# Microcontroller.net
KiCad netlist of a schematic drawn in Altium Designer
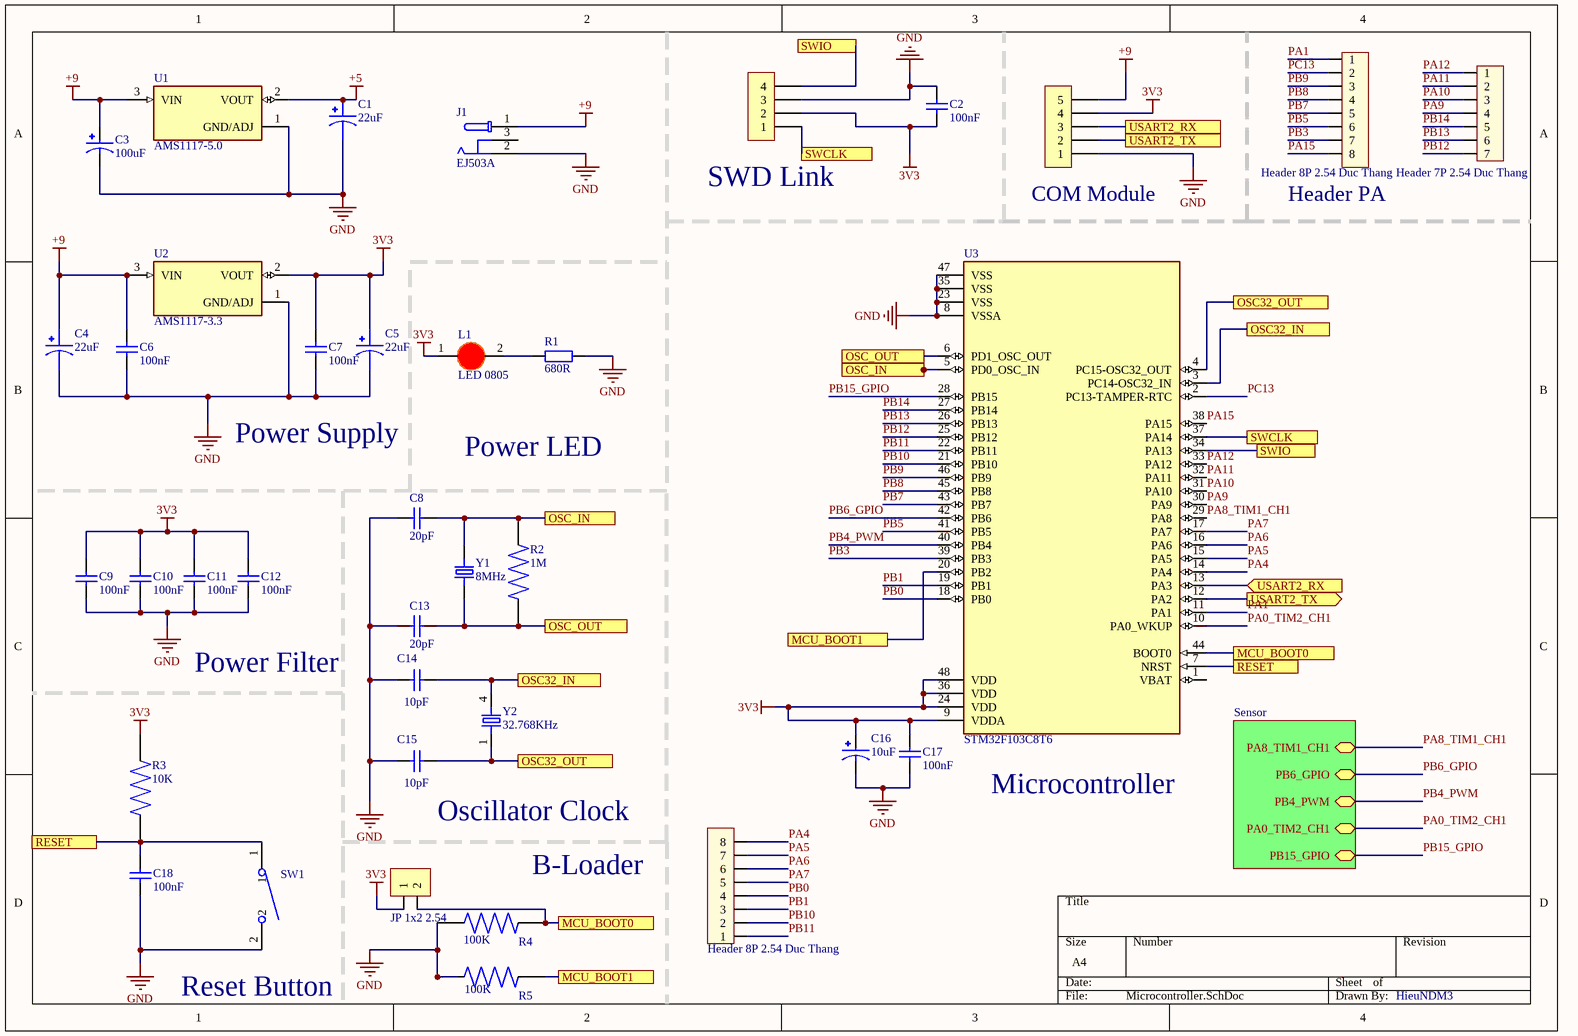
[diagram p0: Microcontroller.SchDoc]

(export (version "E")
  (design (tool "Eeschema 10.0.6"))
  (components
    (comp (ref "C1")
      (value "22uF")
      (footprint "MyPCBLib:CAPPRD200W50D550H1250")
      (description "22ÂµF 25V Aluminum Electrolytic Capacitors Radial, Can 2000 Hrs @ 85Â°C")
      (fields (field (name "MF") "Nichicon") (field (name "MP") "UVR1E220MDD"))
      (libsource (lib "MyScheLib") (part "UVR1E220MDD"))
    )
    (comp (ref "C2")
      (value "100nF")
      (footprint "MyPCBLib:WCAP-CSST_0805_L2W1.25H1.25")
      (fields
        (field (name "MANUFACTURER PART NUMBER") "885382207007")
        (field (name "MANUFACTURER") "Wurth Elektronik")
      )
      (libsource (lib "MyScheLib") (part "885382207007"))
    )
    (comp (ref "C3")
      (value "100uF")
      (footprint "MyPCBLib:CAPPRD500W60D1000H1250")
      (description "CAP ALUM 100UF 20% 35V RADIAL")
      (fields (field (name "MF") "Panasonic") (field (name "MP") "EEUTA1V101"))
      (libsource (lib "MyScheLib") (part "EEUTA1V101"))
    )
    (comp (ref "C4")
      (value "22uF")
      (footprint "MyPCBLib:CAPPRD200W50D550H1250")
      (description "22ÂµF 25V Aluminum Electrolytic Capacitors Radial, Can 2000 Hrs @ 85Â°C")
      (fields (field (name "MF") "Nichicon") (field (name "MP") "UVR1E220MDD"))
      (libsource (lib "MyScheLib") (part "UVR1E220MDD"))
    )
    (comp (ref "C5")
      (value "22uF")
      (footprint "MyPCBLib:CAPPRD200W50D550H1250")
      (description "22ÂµF 25V Aluminum Electrolytic Capacitors Radial, Can 2000 Hrs @ 85Â°C")
      (fields (field (name "MF") "Nichicon") (field (name "MP") "UVR1E220MDD"))
      (libsource (lib "MyScheLib") (part "UVR1E220MDD"))
    )
    (comp (ref "C6")
      (value "100nF")
      (footprint "MyPCBLib:WCAP-CSST_0805_L2W1.25H1.25")
      (fields
        (field (name "MANUFACTURER PART NUMBER") "885382207007")
        (field (name "MANUFACTURER") "Wurth Elektronik")
      )
      (libsource (lib "MyScheLib") (part "885382207007"))
    )
    (comp (ref "C7")
      (value "100nF")
      (footprint "MyPCBLib:WCAP-CSST_0805_L2W1.25H1.25")
      (fields
        (field (name "MANUFACTURER PART NUMBER") "885382207007")
        (field (name "MANUFACTURER") "Wurth Elektronik")
      )
      (libsource (lib "MyScheLib") (part "885382207007"))
    )
    (comp (ref "C8")
      (value "20pF")
      (footprint "tu 0805")
      (description "Dán")
      (libsource (lib "Tu dien") (part "Tu 0805 20pF 50V 10%"))
    )
    (comp (ref "C9")
      (value "100nF")
      (footprint "MyPCBLib:WCAP-CSST_0805_L2W1.25H1.25")
      (fields
        (field (name "MANUFACTURER PART NUMBER") "885382207007")
        (field (name "MANUFACTURER") "Wurth Elektronik")
      )
      (libsource (lib "MyScheLib") (part "885382207007"))
    )
    (comp (ref "C10")
      (value "100nF")
      (footprint "MyPCBLib:WCAP-CSST_0805_L2W1.25H1.25")
      (fields
        (field (name "MANUFACTURER PART NUMBER") "885382207007")
        (field (name "MANUFACTURER") "Wurth Elektronik")
      )
      (libsource (lib "MyScheLib") (part "885382207007"))
    )
    (comp (ref "C11")
      (value "100nF")
      (footprint "MyPCBLib:WCAP-CSST_0805_L2W1.25H1.25")
      (fields
        (field (name "MANUFACTURER PART NUMBER") "885382207007")
        (field (name "MANUFACTURER") "Wurth Elektronik")
      )
      (libsource (lib "MyScheLib") (part "885382207007"))
    )
    (comp (ref "C12")
      (value "100nF")
      (footprint "MyPCBLib:WCAP-CSST_0805_L2W1.25H1.25")
      (fields
        (field (name "MANUFACTURER PART NUMBER") "885382207007")
        (field (name "MANUFACTURER") "Wurth Elektronik")
      )
      (libsource (lib "MyScheLib") (part "885382207007"))
    )
    (comp (ref "C13")
      (value "20pF")
      (footprint "tu 0805")
      (description "Dán")
      (libsource (lib "Tu dien") (part "Tu 0805 20pF 50V 10%"))
    )
    (comp (ref "C14")
      (value "10pF")
      (footprint "WCAP-CSGP_0805_L2W1.25H0.6_Reflow")
      (description "WCAP-CSGP Multilayer Ceramic Chip Capacitor, General Purpose, size 0805, NP0, 10pF, 50V")
      (fields
        (field (name "MANUFACTURER PART NUMBER") "885012007051")
        (field (name "MANUFACTURER") "Wurth Elektronik")
      )
      (libsource (lib "MyScheLib") (part "885012007051"))
    )
    (comp (ref "C15")
      (value "10pF")
      (footprint "WCAP-CSGP_0805_L2W1.25H0.6_Reflow")
      (description "WCAP-CSGP Multilayer Ceramic Chip Capacitor, General Purpose, size 0805, NP0, 10pF, 50V")
      (fields
        (field (name "MANUFACTURER PART NUMBER") "885012007051")
        (field (name "MANUFACTURER") "Wurth Elektronik")
      )
      (libsource (lib "MyScheLib") (part "885012007051"))
    )
    (comp (ref "C16")
      (value "10uF")
      (footprint "MyPCBLib:CAPMP7343X430N")
      (fields (field (name "MF") "Kemet") (field (name "MP") "T493X106K035AK6120"))
      (libsource (lib "MyScheLib") (part "T493X106K035AK6120"))
    )
    (comp (ref "C17")
      (value "100nF")
      (footprint "MyPCBLib:WCAP-CSST_0805_L2W1.25H1.25")
      (fields
        (field (name "MANUFACTURER PART NUMBER") "885382207007")
        (field (name "MANUFACTURER") "Wurth Elektronik")
      )
      (libsource (lib "MyScheLib") (part "885382207007"))
    )
    (comp (ref "C18")
      (value "100nF")
      (footprint "MyPCBLib:WCAP-CSST_0805_L2W1.25H1.25")
      (fields
        (field (name "MANUFACTURER PART NUMBER") "885382207007")
        (field (name "MANUFACTURER") "Wurth Elektronik")
      )
      (libsource (lib "MyScheLib") (part "885382207007"))
    )
    (comp (ref "H1")
      (value "Header 8P 2.54 Duc Thang")
      (footprint "XH2.54M-8")
      (description "Cắm")
      (libsource (lib "Header") (part "Header 8P 2.54 Duc Thang"))
    )
    (comp (ref "H2")
      (value "Header 7P 2.54 Duc Thang")
      (footprint "XH2.54M-7")
      (description "Cắm")
      (libsource (lib "Header") (part "Header 7P 2.54 Duc Thang"))
    )
    (comp (ref "H3")
      (value "~")
      (footprint "Header 4P DC 2.54")
      (description "Cắm")
      (libsource (lib "Header") (part "Header 4P 2.54 Duc Cong"))
    )
    (comp (ref "H4")
      (value "~")
      (footprint "XH2.54M-5")
      (description "Cắm")
      (libsource (lib "Header") (part "Header 5P 2.54 Duc Thang"))
    )
    (comp (ref "H5")
      (value "Header 8P 2.54 Duc Thang")
      (footprint "XH2.54M-8")
      (description "Cắm")
      (libsource (lib "") (part "Header 8P 2.54 Duc Thang_1"))
    )
    (comp (ref "J1")
      (value "EJ503A")
      (footprint "MPD_EJ503A")
      (description "Power Barrel Connector Jack 2.10mm ID (0.083), 5.50mm OD (0.217) Through Hole, Right Angle")
      (fields (field (name "MF") "MPD"))
      (libsource (lib "MyScheLib") (part "EJ503A"))
    )
    (comp (ref "JP1")
      (value "JP 1x2 2.54")
      (footprint "JP 1x2 DT")
      (description "Cắm")
      (libsource (lib "MyScheLib") (part "JP 1x2 2.54 Duc Thang"))
    )
    (comp (ref "L1")
      (value "LED 0805")
      (footprint "LED-0805-Red")
      (description "Dán")
      (libsource (lib "Led") (part "LED 0805 Do"))
    )
    (comp (ref "R1")
      (value "680R")
      (footprint "Tro SMD 0805")
      (description "Dán")
      (libsource (lib "Dien Tro") (part "Tro 0805 5% 680R"))
    )
    (comp (ref "R2")
      (value "1M")
      (footprint "MyPCBLib:RESC2012X65N")
      (description "Res Thin Film 0805 1M Ohm 0.1% 0.125W(1/8W) Â±15ppm/C Epoxy Pad SMD T/R")
      (fields (field (name "MP") "RP73D2A1M0BTDF"))
      (libsource (lib "MyScheLib") (part "RP73D2A1M0BTDF"))
    )
    (comp (ref "R3")
      (value "10K")
      (footprint "RESC2012X65N")
      (fields
        (field (name "MF") "{'manufacturer': u'Stackpole Electronics Inc'}")
        (field (name "MP") "RMCF0805FT10K0")
      )
      (libsource (lib "MyScheLib") (part "RMCF0805FT10K0"))
    )
    (comp (ref "R4")
      (value "100K")
      (footprint "RESC2012X65N")
      (fields
        (field (name "MF") "{'manufacturer': u'Stackpole Electronics Inc'}")
        (field (name "MP") "RMCF0805FT10K0")
      )
      (libsource (lib "MyScheLib") (part "RMCF0805FT10K0"))
    )
    (comp (ref "R5")
      (value "100K")
      (footprint "RESC2012X65N")
      (fields
        (field (name "MF") "{'manufacturer': u'Stackpole Electronics Inc'}")
        (field (name "MP") "RMCF0805FT10K0")
      )
      (libsource (lib "MyScheLib") (part "RMCF0805FT10K0"))
    )
    (comp (ref "SW1")
      (value "~")
      (footprint "MyPCBLib:SW_RS-032G05A3-SMRT")
      (description "Tactile Switch SPST-NO Top Actuated Surface Mount")
      (fields (field (name "MF") "C&K") (field (name "MP") "RS032G05A3SMRT"))
      (libsource (lib "MyScheLib") (part "RS-032G05A3-SMRT"))
    )
    (comp (ref "U1")
      (value "AMS1117-5.0")
      (footprint "SOT229P700X180-4N")
      (description "1A LOW DROPOUT VOLTAGE REGULATOR")
      (fields (field (name "MF") "ams"))
      (libsource (lib "MyScheLib") (part "AMS1117-5.0"))
    )
    (comp (ref "U2")
      (value "AMS1117-3.3")
      (footprint "SOT229P700X180-4N")
      (description "Sot223/Pkg 1-Amp 3.3-Volt Low Drop Out Voltage Regulatator")
      (fields (field (name "MF") "Advanced Monolithic Systems"))
      (libsource (lib "MyScheLib") (part "AMS1117-3.3"))
    )
    (comp (ref "U3")
      (value "STM32F103C8T6")
      (footprint "MyPCBLib:QFP50P900X900X160-48N")
      (description "ARM® Cortex®-M3 STM32F1 Microcontroller IC 32-Bit 72MHz 64KB (64K x 8) FLASH 48-LQFP (7x7)")
      (fields (field (name "MF") "STMicroelectronics"))
      (libsource (lib "MyScheLib") (part "STM32F103C8T6"))
    )
    (comp (ref "Y1")
      (value "8MHz")
      (footprint "MyPCBLib:XTAL_ECS-80-S-4X")
      (description "CRYSTAL T/H")
      (fields (field (name "MP") "ECS-80-S-4X"))
      (libsource (lib "MyScheLib") (part "ECS-80-S-4X"))
    )
    (comp (ref "Y2")
      (value "32.768KHz")
      (footprint "MyPCBLib:OSCL550P800X320X254-4N")
      (description "32.768kHz Â±100ppm Crystal 12.5pF 50 kOhms 4-SOJ, 5.50mm pitch")
      (fields (field (name "MP") "MC-306 32.7680K-A5: ROHS") (field (name "MF") "EPSON"))
      (libsource (lib "MyScheLib") (part "MC-306_32.7680K-A5{colon}_ROHS"))
    )
  )
  (nets
    (net (code "1") (name "+5") (class "Default")
      (node (ref "C1") (pin "1") (pinfunction "1_1") (pintype "passive"))
      (node (ref "U1") (pin "2") (pinfunction "VOUT_2") (pintype "bidirectional"))
    )
    (net (code "2") (name "+9") (class "Default")
      (node (ref "C3") (pin "P") (pinfunction "P_P") (pintype "passive"))
      (node (ref "C4") (pin "1") (pinfunction "1_1") (pintype "passive"))
      (node (ref "C6") (pin "2") (pinfunction "2_2") (pintype "passive"))
      (node (ref "H4") (pin "5") (pinfunction "5_5") (pintype "passive"))
      (node (ref "J1") (pin "1") (pinfunction "1_1") (pintype "passive"))
      (node (ref "U1") (pin "3") (pinfunction "VIN_3") (pintype "input"))
      (node (ref "U2") (pin "3") (pinfunction "VIN_3") (pintype "input"))
    )
    (net (code "3") (name "/MCU_BOOT0") (class "Default")
      (node (ref "JP1") (pin "2") (pinfunction "2_2") (pintype "passive"))
      (node (ref "R4") (pin "1") (pinfunction "1_1") (pintype "passive"))
      (node (ref "U3") (pin "44") (pinfunction "BOOT0_44") (pintype "input"))
    )
    (net (code "4") (name "/MCU_BOOT1") (class "Default")
      (node (ref "R5") (pin "1") (pinfunction "1_1") (pintype "passive"))
      (node (ref "U3") (pin "20") (pinfunction "PB2_20") (pintype "bidirectional"))
    )
    (net (code "5") (name "/OSC32_IN") (class "Default")
      (node (ref "C14") (pin "2") (pinfunction "2_2") (pintype "passive"))
      (node (ref "U3") (pin "3") (pinfunction "PC14-OSC32_IN_3") (pintype "bidirectional"))
      (node (ref "Y2") (pin "4") (pinfunction "4_4") (pintype "passive"))
    )
    (net (code "6") (name "/OSC32_OUT") (class "Default")
      (node (ref "C15") (pin "2") (pinfunction "2_2") (pintype "passive"))
      (node (ref "U3") (pin "4") (pinfunction "PC15-OSC32_OUT_4") (pintype "bidirectional"))
      (node (ref "Y2") (pin "1") (pinfunction "1_1") (pintype "passive"))
    )
    (net (code "7") (name "/OSC_IN") (class "Default")
      (node (ref "C8") (pin "1") (pinfunction "1_1") (pintype "passive"))
      (node (ref "R2") (pin "1") (pinfunction "1_1") (pintype "passive"))
      (node (ref "U3") (pin "5") (pinfunction "PD0_OSC_IN_5") (pintype "bidirectional"))
      (node (ref "Y1") (pin "2") (pinfunction "2_2") (pintype "passive"))
    )
    (net (code "8") (name "/OSC_OUT") (class "Default")
      (node (ref "C13") (pin "1") (pinfunction "1_1") (pintype "passive"))
      (node (ref "R2") (pin "2") (pinfunction "2_2") (pintype "passive"))
      (node (ref "U3") (pin "6") (pinfunction "PD1_OSC_OUT_6") (pintype "bidirectional"))
      (node (ref "Y1") (pin "1") (pinfunction "1_1") (pintype "passive"))
    )
    (net (code "9") (name "/PA0_TIM2_CH1") (class "Default")
      (node (ref "U3") (pin "10") (pinfunction "PA0_WKUP_10") (pintype "bidirectional"))
    )
    (net (code "10") (name "/PA1") (class "Default")
      (node (ref "H1") (pin "1") (pinfunction "1_1") (pintype "passive"))
      (node (ref "U3") (pin "11") (pinfunction "PA1_11") (pintype "bidirectional"))
    )
    (net (code "11") (name "/PA4") (class "Default")
      (node (ref "H5") (pin "8") (pinfunction "8_8") (pintype "passive"))
      (node (ref "U3") (pin "14") (pinfunction "PA4_14") (pintype "bidirectional"))
    )
    (net (code "12") (name "/PA5") (class "Default")
      (node (ref "H5") (pin "7") (pinfunction "7_7") (pintype "passive"))
      (node (ref "U3") (pin "15") (pinfunction "PA5_15") (pintype "bidirectional"))
    )
    (net (code "13") (name "/PA6") (class "Default")
      (node (ref "H5") (pin "6") (pinfunction "6_6") (pintype "passive"))
      (node (ref "U3") (pin "16") (pinfunction "PA6_16") (pintype "bidirectional"))
    )
    (net (code "14") (name "/PA7") (class "Default")
      (node (ref "H5") (pin "5") (pinfunction "5_5") (pintype "passive"))
      (node (ref "U3") (pin "17") (pinfunction "PA7_17") (pintype "bidirectional"))
    )
    (net (code "15") (name "/PA8_TIM1_CH1") (class "Default")
      (node (ref "U3") (pin "29") (pinfunction "PA8_29") (pintype "bidirectional"))
    )
    (net (code "16") (name "/PA9") (class "Default")
      (node (ref "H2") (pin "4") (pinfunction "4_4") (pintype "passive"))
      (node (ref "U3") (pin "30") (pinfunction "PA9_30") (pintype "bidirectional"))
    )
    (net (code "17") (name "/PA10") (class "Default")
      (node (ref "H2") (pin "3") (pinfunction "3_3") (pintype "passive"))
      (node (ref "U3") (pin "31") (pinfunction "PA10_31") (pintype "bidirectional"))
    )
    (net (code "18") (name "/PA11") (class "Default")
      (node (ref "H2") (pin "2") (pinfunction "2_2") (pintype "passive"))
      (node (ref "U3") (pin "32") (pinfunction "PA11_32") (pintype "bidirectional"))
    )
    (net (code "19") (name "/PA12") (class "Default")
      (node (ref "H2") (pin "1") (pinfunction "1_1") (pintype "passive"))
      (node (ref "U3") (pin "33") (pinfunction "PA12_33") (pintype "bidirectional"))
    )
    (net (code "20") (name "/PA15") (class "Default")
      (node (ref "H1") (pin "8") (pinfunction "8_8") (pintype "passive"))
      (node (ref "U3") (pin "38") (pinfunction "PA15_38") (pintype "bidirectional"))
    )
    (net (code "21") (name "/PB0") (class "Default")
      (node (ref "H5") (pin "4") (pinfunction "4_4") (pintype "passive"))
      (node (ref "U3") (pin "18") (pinfunction "PB0_18") (pintype "bidirectional"))
    )
    (net (code "22") (name "/PB1") (class "Default")
      (node (ref "H5") (pin "3") (pinfunction "3_3") (pintype "passive"))
      (node (ref "U3") (pin "19") (pinfunction "PB1_19") (pintype "bidirectional"))
    )
    (net (code "23") (name "/PB3") (class "Default")
      (node (ref "H1") (pin "7") (pinfunction "7_7") (pintype "passive"))
      (node (ref "U3") (pin "39") (pinfunction "PB3_39") (pintype "bidirectional"))
    )
    (net (code "24") (name "/PB4_PWM") (class "Default")
      (node (ref "U3") (pin "40") (pinfunction "PB4_40") (pintype "bidirectional"))
    )
    (net (code "25") (name "/PB5") (class "Default")
      (node (ref "H1") (pin "6") (pinfunction "6_6") (pintype "passive"))
      (node (ref "U3") (pin "41") (pinfunction "PB5_41") (pintype "bidirectional"))
    )
    (net (code "26") (name "/PB6_GPIO") (class "Default")
      (node (ref "U3") (pin "42") (pinfunction "PB6_42") (pintype "bidirectional"))
    )
    (net (code "27") (name "/PB7") (class "Default")
      (node (ref "H1") (pin "5") (pinfunction "5_5") (pintype "passive"))
      (node (ref "U3") (pin "43") (pinfunction "PB7_43") (pintype "bidirectional"))
    )
    (net (code "28") (name "/PB8") (class "Default")
      (node (ref "H1") (pin "4") (pinfunction "4_4") (pintype "passive"))
      (node (ref "U3") (pin "45") (pinfunction "PB8_45") (pintype "bidirectional"))
    )
    (net (code "29") (name "/PB9") (class "Default")
      (node (ref "H1") (pin "3") (pinfunction "3_3") (pintype "passive"))
      (node (ref "U3") (pin "46") (pinfunction "PB9_46") (pintype "bidirectional"))
    )
    (net (code "30") (name "/PB10") (class "Default")
      (node (ref "H5") (pin "2") (pinfunction "2_2") (pintype "passive"))
      (node (ref "U3") (pin "21") (pinfunction "PB10_21") (pintype "bidirectional"))
    )
    (net (code "31") (name "/PB11") (class "Default")
      (node (ref "H5") (pin "1") (pinfunction "1_1") (pintype "passive"))
      (node (ref "U3") (pin "22") (pinfunction "PB11_22") (pintype "bidirectional"))
    )
    (net (code "32") (name "/PB12") (class "Default")
      (node (ref "H2") (pin "7") (pinfunction "7_7") (pintype "passive"))
      (node (ref "U3") (pin "25") (pinfunction "PB12_25") (pintype "bidirectional"))
    )
    (net (code "33") (name "/PB13") (class "Default")
      (node (ref "H2") (pin "6") (pinfunction "6_6") (pintype "passive"))
      (node (ref "U3") (pin "26") (pinfunction "PB13_26") (pintype "bidirectional"))
    )
    (net (code "34") (name "/PB14") (class "Default")
      (node (ref "H2") (pin "5") (pinfunction "5_5") (pintype "passive"))
      (node (ref "U3") (pin "27") (pinfunction "PB14_27") (pintype "bidirectional"))
    )
    (net (code "35") (name "/PB15_GPIO") (class "Default")
      (node (ref "U3") (pin "28") (pinfunction "PB15_28") (pintype "bidirectional"))
    )
    (net (code "36") (name "/PC13") (class "Default")
      (node (ref "H1") (pin "2") (pinfunction "2_2") (pintype "passive"))
      (node (ref "U3") (pin "2") (pinfunction "PC13-TAMPER-RTC_2") (pintype "bidirectional"))
    )
    (net (code "37") (name "/RESET") (class "Default")
      (node (ref "C18") (pin "2") (pinfunction "2_2") (pintype "passive"))
      (node (ref "R3") (pin "1") (pinfunction "1_1") (pintype "passive"))
      (node (ref "SW1") (pin "1") (pinfunction "1_1") (pintype "passive"))
      (node (ref "U3") (pin "7") (pinfunction "NRST_7") (pintype "input"))
    )
    (net (code "38") (name "/SWCLK") (class "Default")
      (node (ref "H3") (pin "1") (pinfunction "1_1") (pintype "passive"))
      (node (ref "U3") (pin "37") (pinfunction "PA14_37") (pintype "bidirectional"))
    )
    (net (code "39") (name "/SWIO") (class "Default")
      (node (ref "H3") (pin "4") (pinfunction "4_4") (pintype "passive"))
      (node (ref "U3") (pin "34") (pinfunction "PA13_34") (pintype "bidirectional"))
    )
    (net (code "40") (name "/USART2_RX") (class "Default")
      (node (ref "H4") (pin "3") (pinfunction "3_3") (pintype "passive"))
      (node (ref "U3") (pin "13") (pinfunction "PA3_13") (pintype "bidirectional"))
    )
    (net (code "41") (name "/USART2_TX") (class "Default")
      (node (ref "H4") (pin "2") (pinfunction "2_2") (pintype "passive"))
      (node (ref "U3") (pin "12") (pinfunction "PA2_12") (pintype "bidirectional"))
    )
    (net (code "42") (name "3V3") (class "Default")
      (node (ref "C10") (pin "2") (pinfunction "2_2") (pintype "passive"))
      (node (ref "C11") (pin "2") (pinfunction "2_2") (pintype "passive"))
      (node (ref "C12") (pin "2") (pinfunction "2_2") (pintype "passive"))
      (node (ref "C16") (pin "1") (pinfunction "1_1") (pintype "passive"))
      (node (ref "C17") (pin "2") (pinfunction "2_2") (pintype "passive"))
      (node (ref "C2") (pin "1") (pinfunction "1_1") (pintype "passive"))
      (node (ref "C5") (pin "1") (pinfunction "1_1") (pintype "passive"))
      (node (ref "C7") (pin "2") (pinfunction "2_2") (pintype "passive"))
      (node (ref "C9") (pin "2") (pinfunction "2_2") (pintype "passive"))
      (node (ref "H3") (pin "2") (pinfunction "2_2") (pintype "passive"))
      (node (ref "H4") (pin "4") (pinfunction "4_4") (pintype "passive"))
      (node (ref "JP1") (pin "1") (pinfunction "1_1") (pintype "passive"))
      (node (ref "L1") (pin "1") (pinfunction "A_1") (pintype "passive"))
      (node (ref "R3") (pin "2") (pinfunction "2_2") (pintype "passive"))
      (node (ref "U2") (pin "2") (pinfunction "VOUT_2") (pintype "bidirectional"))
      (node (ref "U3") (pin "24") (pinfunction "VDD_24") (pintype "power_in"))
      (node (ref "U3") (pin "36") (pinfunction "VDD_36") (pintype "power_in"))
      (node (ref "U3") (pin "48") (pinfunction "VDD_48") (pintype "power_in"))
      (node (ref "U3") (pin "9") (pinfunction "VDDA_9") (pintype "power_in"))
    )
    (net (code "43") (name "GND") (class "Default")
      (node (ref "C1") (pin "2") (pinfunction "2_2") (pintype "passive"))
      (node (ref "C10") (pin "1") (pinfunction "1_1") (pintype "passive"))
      (node (ref "C11") (pin "1") (pinfunction "1_1") (pintype "passive"))
      (node (ref "C12") (pin "1") (pinfunction "1_1") (pintype "passive"))
      (node (ref "C13") (pin "2") (pinfunction "2_2") (pintype "passive"))
      (node (ref "C14") (pin "1") (pinfunction "1_1") (pintype "passive"))
      (node (ref "C15") (pin "1") (pinfunction "1_1") (pintype "passive"))
      (node (ref "C16") (pin "2") (pinfunction "2_2") (pintype "passive"))
      (node (ref "C17") (pin "1") (pinfunction "1_1") (pintype "passive"))
      (node (ref "C18") (pin "1") (pinfunction "1_1") (pintype "passive"))
      (node (ref "C2") (pin "2") (pinfunction "2_2") (pintype "passive"))
      (node (ref "C3") (pin "N") (pinfunction "N_N") (pintype "passive"))
      (node (ref "C4") (pin "2") (pinfunction "2_2") (pintype "passive"))
      (node (ref "C5") (pin "2") (pinfunction "2_2") (pintype "passive"))
      (node (ref "C6") (pin "1") (pinfunction "1_1") (pintype "passive"))
      (node (ref "C7") (pin "1") (pinfunction "1_1") (pintype "passive"))
      (node (ref "C8") (pin "2") (pinfunction "2_2") (pintype "passive"))
      (node (ref "C9") (pin "1") (pinfunction "1_1") (pintype "passive"))
      (node (ref "H3") (pin "3") (pinfunction "3_3") (pintype "passive"))
      (node (ref "H4") (pin "1") (pinfunction "1_1") (pintype "passive"))
      (node (ref "J1") (pin "2") (pinfunction "2_2") (pintype "passive"))
      (node (ref "R1") (pin "2") (pinfunction "2_2") (pintype "passive"))
      (node (ref "R4") (pin "2") (pinfunction "2_2") (pintype "passive"))
      (node (ref "R5") (pin "2") (pinfunction "2_2") (pintype "passive"))
      (node (ref "SW1") (pin "2") (pinfunction "2_2") (pintype "passive"))
      (node (ref "U1") (pin "1") (pinfunction "GND/ADJ_1") (pintype "power_in"))
      (node (ref "U2") (pin "1") (pinfunction "GND/ADJ_1") (pintype "power_in"))
      (node (ref "U3") (pin "23") (pinfunction "VSS_23") (pintype "power_in"))
      (node (ref "U3") (pin "35") (pinfunction "VSS_35") (pintype "power_in"))
      (node (ref "U3") (pin "47") (pinfunction "VSS_47") (pintype "power_in"))
      (node (ref "U3") (pin "8") (pinfunction "VSSA_8") (pintype "power_in"))
    )
    (net (code "44") (name "Net-(L1-K)") (class "Default")
      (node (ref "L1") (pin "2") (pinfunction "K_2") (pintype "passive"))
      (node (ref "R1") (pin "1") (pinfunction "1_1") (pintype "passive"))
    )
    (net (code "45") (name "unconnected-(J1-Pad3)") (class "Default")
      (node (ref "J1") (pin "3") (pinfunction "3_3") (pintype "passive"))
    )
    (net (code "46") (name "unconnected-(U3-VBAT-Pad1)") (class "Default")
      (node (ref "U3") (pin "1") (pinfunction "VBAT_1") (pintype "bidirectional"))
    )
  )
)
